# FPGA.net
KiCad netlist of a schematic drawn in Altium Designer
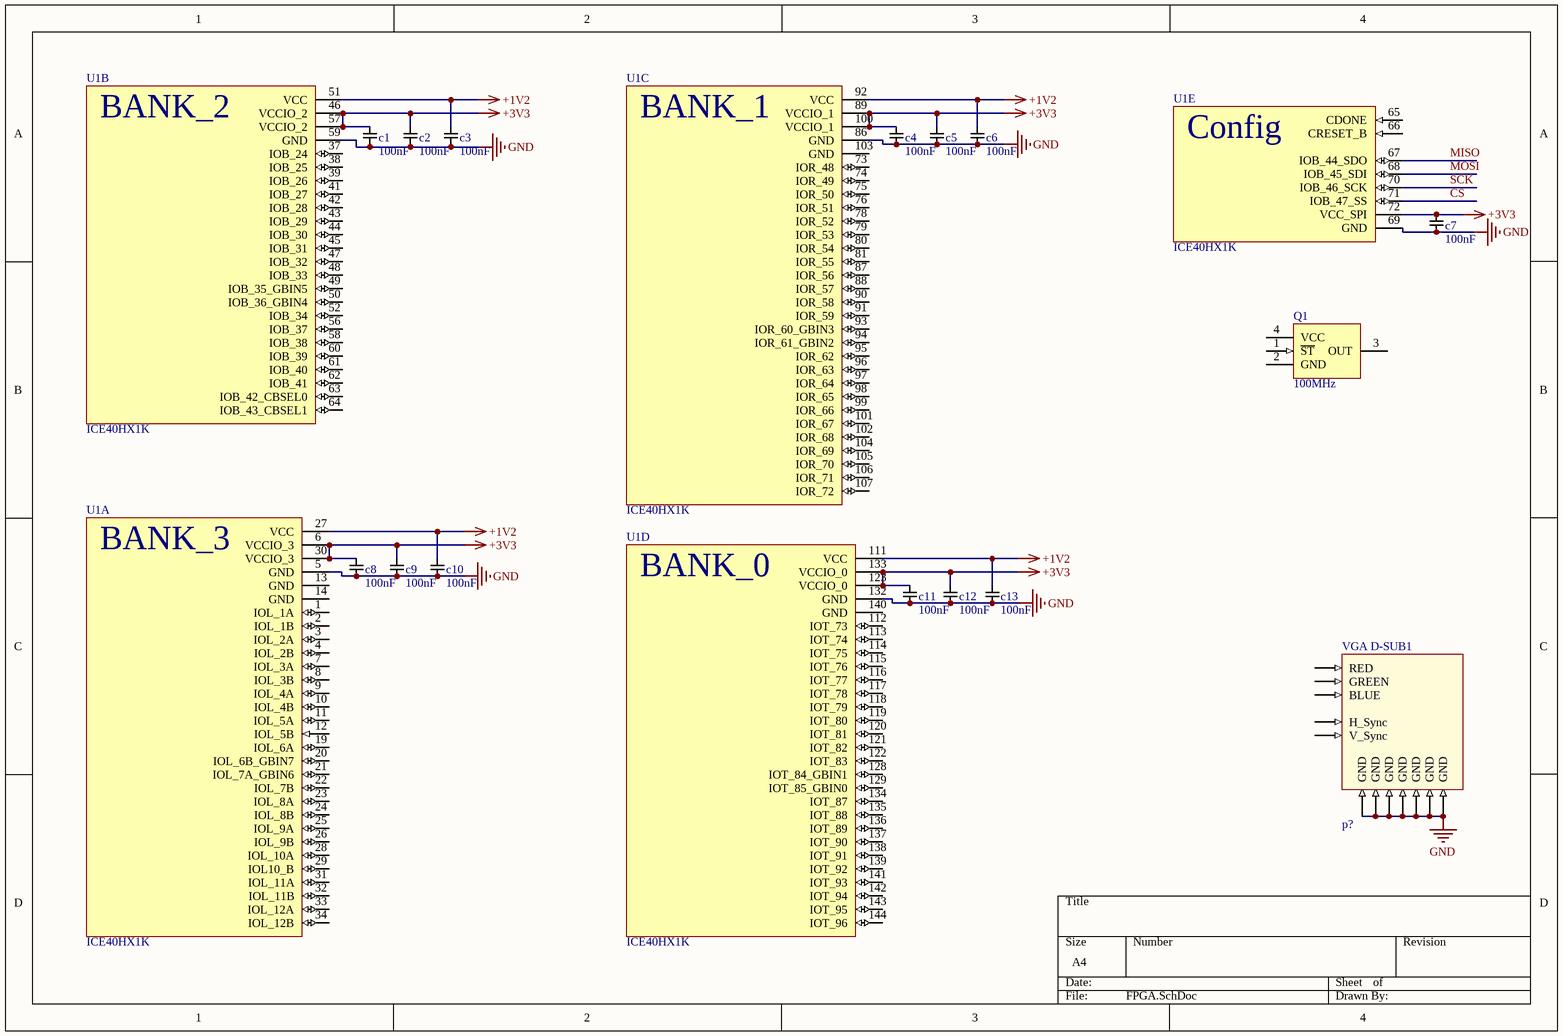
[diagram p0: FPGA.SchDoc]

(export (version "E")
  (design (tool "Eeschema 10.0.6"))
  (components
    (comp (ref "c1")
      (value "100nF")
      (footprint "0603")
      (description "...F")
      (libsource (lib "Generic R-C") (part "0603 Capacitor"))
    )
    (comp (ref "c2")
      (value "100nF")
      (footprint "0603")
      (description "...F")
      (libsource (lib "Generic R-C") (part "0603 Capacitor"))
    )
    (comp (ref "c3")
      (value "100nF")
      (footprint "0603")
      (description "...F")
      (libsource (lib "Generic R-C") (part "0603 Capacitor"))
    )
    (comp (ref "c4")
      (value "100nF")
      (footprint "0603")
      (description "...F")
      (libsource (lib "Generic R-C") (part "0603 Capacitor"))
    )
    (comp (ref "c5")
      (value "100nF")
      (footprint "0603")
      (description "...F")
      (libsource (lib "Generic R-C") (part "0603 Capacitor"))
    )
    (comp (ref "c6")
      (value "100nF")
      (footprint "0603")
      (description "...F")
      (libsource (lib "Generic R-C") (part "0603 Capacitor"))
    )
    (comp (ref "c7")
      (value "100nF")
      (footprint "0603")
      (description "...F")
      (libsource (lib "Generic R-C") (part "0603 Capacitor"))
    )
    (comp (ref "c8")
      (value "100nF")
      (footprint "0603")
      (description "...F")
      (libsource (lib "Generic R-C") (part "0603 Capacitor"))
    )
    (comp (ref "c9")
      (value "100nF")
      (footprint "0603")
      (description "...F")
      (libsource (lib "Generic R-C") (part "0603 Capacitor"))
    )
    (comp (ref "c10")
      (value "100nF")
      (footprint "0603")
      (description "...F")
      (libsource (lib "Generic R-C") (part "0603 Capacitor"))
    )
    (comp (ref "c11")
      (value "100nF")
      (footprint "0603")
      (description "...F")
      (libsource (lib "Generic R-C") (part "0603 Capacitor"))
    )
    (comp (ref "c12")
      (value "100nF")
      (footprint "0603")
      (description "...F")
      (libsource (lib "Generic R-C") (part "0603 Capacitor"))
    )
    (comp (ref "c13")
      (value "100nF")
      (footprint "0603")
      (description "...F")
      (libsource (lib "Generic R-C") (part "0603 Capacitor"))
    )
    (comp (ref "Q1")
      (value "100MHz")
      (footprint "Crystal Oscillator-2.5X2mm")
      (description "Crystal Oscillator")
      (libsource (lib "Seiko Epson Corp.") (part "SG-210S*H"))
    )
    (comp (ref "U1")
      (value "ICE40HX1K")
      (footprint "TQFP-144")
      (description "ICE40 FPGA TQFP-144")
      (libsource (lib "Lattice") (part "ICE40HX1K"))
    )
    (comp (ref "VGA D-SUB1")
      (value "p?")
      (footprint "SUB-D15_VGA")
      (description "VGA receptor")
      (libsource (lib "EDAC") (part "VGA connector"))
    )
  )
  (nets
    (net (code "1") (name "+1V2") (class "Default")
      (node (ref "U1") (pin "111") (pinfunction "VCC_111") (pintype "power_in"))
      (node (ref "U1") (pin "27") (pinfunction "VCC_27") (pintype "power_in"))
      (node (ref "U1") (pin "51") (pinfunction "VCC_51") (pintype "power_in"))
      (node (ref "U1") (pin "92") (pinfunction "VCC_92") (pintype "power_in"))
      (node (ref "c10") (pin "2") (pinfunction "2_2") (pintype "passive"))
      (node (ref "c13") (pin "2") (pinfunction "2_2") (pintype "passive"))
      (node (ref "c3") (pin "2") (pinfunction "2_2") (pintype "passive"))
      (node (ref "c6") (pin "2") (pinfunction "2_2") (pintype "passive"))
    )
    (net (code "2") (name "+3V3") (class "Default")
      (node (ref "U1") (pin "100") (pinfunction "VCCIO_1_100") (pintype "power_in"))
      (node (ref "U1") (pin "123") (pinfunction "VCCIO_0_123") (pintype "power_in"))
      (node (ref "U1") (pin "133") (pinfunction "VCCIO_0_133") (pintype "power_in"))
      (node (ref "U1") (pin "30") (pinfunction "VCCIO_3_30") (pintype "power_in"))
      (node (ref "U1") (pin "46") (pinfunction "VCCIO_2_46") (pintype "power_in"))
      (node (ref "U1") (pin "57") (pinfunction "VCCIO_2_57") (pintype "power_in"))
      (node (ref "U1") (pin "6") (pinfunction "VCCIO_3_6") (pintype "power_in"))
      (node (ref "U1") (pin "72") (pinfunction "VCC_SPI_72") (pintype "power_in"))
      (node (ref "U1") (pin "89") (pinfunction "VCCIO_1_89") (pintype "power_in"))
      (node (ref "c1") (pin "2") (pinfunction "2_2") (pintype "passive"))
      (node (ref "c11") (pin "2") (pinfunction "2_2") (pintype "passive"))
      (node (ref "c12") (pin "2") (pinfunction "2_2") (pintype "passive"))
      (node (ref "c2") (pin "2") (pinfunction "2_2") (pintype "passive"))
      (node (ref "c4") (pin "2") (pinfunction "2_2") (pintype "passive"))
      (node (ref "c5") (pin "2") (pinfunction "2_2") (pintype "passive"))
      (node (ref "c7") (pin "2") (pinfunction "2_2") (pintype "passive"))
      (node (ref "c8") (pin "2") (pinfunction "2_2") (pintype "passive"))
      (node (ref "c9") (pin "2") (pinfunction "2_2") (pintype "passive"))
    )
    (net (code "3") (name "/MISO") (class "Default")
      (node (ref "U1") (pin "67") (pinfunction "IOB_44_SDO_67") (pintype "bidirectional"))
    )
    (net (code "4") (name "/MOSI") (class "Default")
      (node (ref "U1") (pin "68") (pinfunction "IOB_45_SDI_68") (pintype "bidirectional"))
    )
    (net (code "5") (name "/SCK") (class "Default")
      (node (ref "U1") (pin "70") (pinfunction "IOB_46_SCK_70") (pintype "bidirectional"))
    )
    (net (code "6") (name "/~{CS}") (class "Default")
      (node (ref "U1") (pin "71") (pinfunction "IOB_47_SS_71") (pintype "bidirectional"))
    )
    (net (code "7") (name "GND") (class "Default")
      (node (ref "U1") (pin "132") (pinfunction "GND_132") (pintype "power_in"))
      (node (ref "U1") (pin "5") (pinfunction "GND_5") (pintype "power_in"))
      (node (ref "U1") (pin "59") (pinfunction "GND_59") (pintype "power_in"))
      (node (ref "U1") (pin "69") (pinfunction "GND_69") (pintype "power_in"))
      (node (ref "U1") (pin "86") (pinfunction "GND_86") (pintype "power_in"))
      (node (ref "VGA D-SUB1") (pin "10") (pinfunction "GND_10") (pintype "input"))
      (node (ref "VGA D-SUB1") (pin "16") (pinfunction "GND_16") (pintype "input"))
      (node (ref "VGA D-SUB1") (pin "17") (pinfunction "GND_17") (pintype "input"))
      (node (ref "VGA D-SUB1") (pin "5") (pinfunction "GND_5") (pintype "input"))
      (node (ref "VGA D-SUB1") (pin "6") (pinfunction "GND_6") (pintype "input"))
      (node (ref "VGA D-SUB1") (pin "7") (pinfunction "GND_7") (pintype "input"))
      (node (ref "VGA D-SUB1") (pin "8") (pinfunction "GND_8") (pintype "input"))
      (node (ref "c1") (pin "1") (pinfunction "1_1") (pintype "passive"))
      (node (ref "c10") (pin "1") (pinfunction "1_1") (pintype "passive"))
      (node (ref "c11") (pin "1") (pinfunction "1_1") (pintype "passive"))
      (node (ref "c12") (pin "1") (pinfunction "1_1") (pintype "passive"))
      (node (ref "c13") (pin "1") (pinfunction "1_1") (pintype "passive"))
      (node (ref "c2") (pin "1") (pinfunction "1_1") (pintype "passive"))
      (node (ref "c3") (pin "1") (pinfunction "1_1") (pintype "passive"))
      (node (ref "c4") (pin "1") (pinfunction "1_1") (pintype "passive"))
      (node (ref "c5") (pin "1") (pinfunction "1_1") (pintype "passive"))
      (node (ref "c6") (pin "1") (pinfunction "1_1") (pintype "passive"))
      (node (ref "c7") (pin "1") (pinfunction "1_1") (pintype "passive"))
      (node (ref "c8") (pin "1") (pinfunction "1_1") (pintype "passive"))
      (node (ref "c9") (pin "1") (pinfunction "1_1") (pintype "passive"))
    )
    (net (code "8") (name "unconnected-(Q1-GND-Pad2)") (class "Default")
      (node (ref "Q1") (pin "2") (pinfunction "GND_2") (pintype "power_in"))
    )
    (net (code "9") (name "unconnected-(Q1-OUT-Pad3)") (class "Default")
      (node (ref "Q1") (pin "3") (pinfunction "OUT_3") (pintype "power_in"))
    )
    (net (code "10") (name "unconnected-(Q1-VCC-Pad4)") (class "Default")
      (node (ref "Q1") (pin "4") (pinfunction "VCC_4") (pintype "power_in"))
    )
    (net (code "11") (name "unconnected-(Q1-~{ST}-Pad1)") (class "Default")
      (node (ref "Q1") (pin "1") (pinfunction "~{ST}_1") (pintype "input"))
    )
    (net (code "12") (name "unconnected-(U1A-GND-Pad13)") (class "Default")
      (node (ref "U1") (pin "13") (pinfunction "GND_13") (pintype "power_in"))
    )
    (net (code "13") (name "unconnected-(U1A-GND-Pad14)") (class "Default")
      (node (ref "U1") (pin "14") (pinfunction "GND_14") (pintype "power_in"))
    )
    (net (code "14") (name "unconnected-(U1A-IOL10_B-Pad29)") (class "Default")
      (node (ref "U1") (pin "29") (pinfunction "IOL10_B_29") (pintype "bidirectional"))
    )
    (net (code "15") (name "unconnected-(U1A-IOL_1A-Pad1)") (class "Default")
      (node (ref "U1") (pin "1") (pinfunction "IOL_1A_1") (pintype "bidirectional"))
    )
    (net (code "16") (name "unconnected-(U1A-IOL_1B-Pad2)") (class "Default")
      (node (ref "U1") (pin "2") (pinfunction "IOL_1B_2") (pintype "bidirectional"))
    )
    (net (code "17") (name "unconnected-(U1A-IOL_2A-Pad3)") (class "Default")
      (node (ref "U1") (pin "3") (pinfunction "IOL_2A_3") (pintype "bidirectional"))
    )
    (net (code "18") (name "unconnected-(U1A-IOL_2B-Pad4)") (class "Default")
      (node (ref "U1") (pin "4") (pinfunction "IOL_2B_4") (pintype "bidirectional"))
    )
    (net (code "19") (name "unconnected-(U1A-IOL_3A-Pad7)") (class "Default")
      (node (ref "U1") (pin "7") (pinfunction "IOL_3A_7") (pintype "bidirectional"))
    )
    (net (code "20") (name "unconnected-(U1A-IOL_3B-Pad8)") (class "Default")
      (node (ref "U1") (pin "8") (pinfunction "IOL_3B_8") (pintype "bidirectional"))
    )
    (net (code "21") (name "unconnected-(U1A-IOL_4A-Pad9)") (class "Default")
      (node (ref "U1") (pin "9") (pinfunction "IOL_4A_9") (pintype "bidirectional"))
    )
    (net (code "22") (name "unconnected-(U1A-IOL_4B-Pad10)") (class "Default")
      (node (ref "U1") (pin "10") (pinfunction "IOL_4B_10") (pintype "bidirectional"))
    )
    (net (code "23") (name "unconnected-(U1A-IOL_5A-Pad11)") (class "Default")
      (node (ref "U1") (pin "11") (pinfunction "IOL_5A_11") (pintype "bidirectional"))
    )
    (net (code "24") (name "unconnected-(U1A-IOL_5B-Pad12)") (class "Default")
      (node (ref "U1") (pin "12") (pinfunction "IOL_5B_12") (pintype "input"))
    )
    (net (code "25") (name "unconnected-(U1A-IOL_6A-Pad19)") (class "Default")
      (node (ref "U1") (pin "19") (pinfunction "IOL_6A_19") (pintype "bidirectional"))
    )
    (net (code "26") (name "unconnected-(U1A-IOL_6B_GBIN7-Pad20)") (class "Default")
      (node (ref "U1") (pin "20") (pinfunction "IOL_6B_GBIN7_20") (pintype "bidirectional"))
    )
    (net (code "27") (name "unconnected-(U1A-IOL_7A_GBIN6-Pad21)") (class "Default")
      (node (ref "U1") (pin "21") (pinfunction "IOL_7A_GBIN6_21") (pintype "bidirectional"))
    )
    (net (code "28") (name "unconnected-(U1A-IOL_7B-Pad22)") (class "Default")
      (node (ref "U1") (pin "22") (pinfunction "IOL_7B_22") (pintype "bidirectional"))
    )
    (net (code "29") (name "unconnected-(U1A-IOL_8A-Pad23)") (class "Default")
      (node (ref "U1") (pin "23") (pinfunction "IOL_8A_23") (pintype "bidirectional"))
    )
    (net (code "30") (name "unconnected-(U1A-IOL_8B-Pad24)") (class "Default")
      (node (ref "U1") (pin "24") (pinfunction "IOL_8B_24") (pintype "bidirectional"))
    )
    (net (code "31") (name "unconnected-(U1A-IOL_9A-Pad25)") (class "Default")
      (node (ref "U1") (pin "25") (pinfunction "IOL_9A_25") (pintype "bidirectional"))
    )
    (net (code "32") (name "unconnected-(U1A-IOL_9B-Pad26)") (class "Default")
      (node (ref "U1") (pin "26") (pinfunction "IOL_9B_26") (pintype "bidirectional"))
    )
    (net (code "33") (name "unconnected-(U1A-IOL_10A-Pad28)") (class "Default")
      (node (ref "U1") (pin "28") (pinfunction "IOL_10A_28") (pintype "bidirectional"))
    )
    (net (code "34") (name "unconnected-(U1A-IOL_11A-Pad31)") (class "Default")
      (node (ref "U1") (pin "31") (pinfunction "IOL_11A_31") (pintype "bidirectional"))
    )
    (net (code "35") (name "unconnected-(U1A-IOL_11B-Pad32)") (class "Default")
      (node (ref "U1") (pin "32") (pinfunction "IOL_11B_32") (pintype "bidirectional"))
    )
    (net (code "36") (name "unconnected-(U1A-IOL_12A-Pad33)") (class "Default")
      (node (ref "U1") (pin "33") (pinfunction "IOL_12A_33") (pintype "bidirectional"))
    )
    (net (code "37") (name "unconnected-(U1A-IOL_12B-Pad34)") (class "Default")
      (node (ref "U1") (pin "34") (pinfunction "IOL_12B_34") (pintype "bidirectional"))
    )
    (net (code "38") (name "unconnected-(U1B-IOB_24-Pad37)") (class "Default")
      (node (ref "U1") (pin "37") (pinfunction "IOB_24_37") (pintype "bidirectional"))
    )
    (net (code "39") (name "unconnected-(U1B-IOB_25-Pad38)") (class "Default")
      (node (ref "U1") (pin "38") (pinfunction "IOB_25_38") (pintype "bidirectional"))
    )
    (net (code "40") (name "unconnected-(U1B-IOB_26-Pad39)") (class "Default")
      (node (ref "U1") (pin "39") (pinfunction "IOB_26_39") (pintype "bidirectional"))
    )
    (net (code "41") (name "unconnected-(U1B-IOB_27-Pad41)") (class "Default")
      (node (ref "U1") (pin "41") (pinfunction "IOB_27_41") (pintype "bidirectional"))
    )
    (net (code "42") (name "unconnected-(U1B-IOB_28-Pad42)") (class "Default")
      (node (ref "U1") (pin "42") (pinfunction "IOB_28_42") (pintype "bidirectional"))
    )
    (net (code "43") (name "unconnected-(U1B-IOB_29-Pad43)") (class "Default")
      (node (ref "U1") (pin "43") (pinfunction "IOB_29_43") (pintype "bidirectional"))
    )
    (net (code "44") (name "unconnected-(U1B-IOB_30-Pad44)") (class "Default")
      (node (ref "U1") (pin "44") (pinfunction "IOB_30_44") (pintype "bidirectional"))
    )
    (net (code "45") (name "unconnected-(U1B-IOB_31-Pad45)") (class "Default")
      (node (ref "U1") (pin "45") (pinfunction "IOB_31_45") (pintype "bidirectional"))
    )
    (net (code "46") (name "unconnected-(U1B-IOB_32-Pad47)") (class "Default")
      (node (ref "U1") (pin "47") (pinfunction "IOB_32_47") (pintype "bidirectional"))
    )
    (net (code "47") (name "unconnected-(U1B-IOB_33-Pad48)") (class "Default")
      (node (ref "U1") (pin "48") (pinfunction "IOB_33_48") (pintype "bidirectional"))
    )
    (net (code "48") (name "unconnected-(U1B-IOB_34-Pad52)") (class "Default")
      (node (ref "U1") (pin "52") (pinfunction "IOB_34_52") (pintype "bidirectional"))
    )
    (net (code "49") (name "unconnected-(U1B-IOB_35_GBIN5-Pad49)") (class "Default")
      (node (ref "U1") (pin "49") (pinfunction "IOB_35_GBIN5_49") (pintype "bidirectional"))
    )
    (net (code "50") (name "unconnected-(U1B-IOB_36_GBIN4-Pad50)") (class "Default")
      (node (ref "U1") (pin "50") (pinfunction "IOB_36_GBIN4_50") (pintype "bidirectional"))
    )
    (net (code "51") (name "unconnected-(U1B-IOB_37-Pad56)") (class "Default")
      (node (ref "U1") (pin "56") (pinfunction "IOB_37_56") (pintype "bidirectional"))
    )
    (net (code "52") (name "unconnected-(U1B-IOB_38-Pad58)") (class "Default")
      (node (ref "U1") (pin "58") (pinfunction "IOB_38_58") (pintype "bidirectional"))
    )
    (net (code "53") (name "unconnected-(U1B-IOB_39-Pad60)") (class "Default")
      (node (ref "U1") (pin "60") (pinfunction "IOB_39_60") (pintype "bidirectional"))
    )
    (net (code "54") (name "unconnected-(U1B-IOB_40-Pad61)") (class "Default")
      (node (ref "U1") (pin "61") (pinfunction "IOB_40_61") (pintype "bidirectional"))
    )
    (net (code "55") (name "unconnected-(U1B-IOB_41-Pad62)") (class "Default")
      (node (ref "U1") (pin "62") (pinfunction "IOB_41_62") (pintype "bidirectional"))
    )
    (net (code "56") (name "unconnected-(U1B-IOB_42_CBSEL0-Pad63)") (class "Default")
      (node (ref "U1") (pin "63") (pinfunction "IOB_42_CBSEL0_63") (pintype "bidirectional"))
    )
    (net (code "57") (name "unconnected-(U1B-IOB_43_CBSEL1-Pad64)") (class "Default")
      (node (ref "U1") (pin "64") (pinfunction "IOB_43_CBSEL1_64") (pintype "bidirectional"))
    )
    (net (code "58") (name "unconnected-(U1C-GND-Pad103)") (class "Default")
      (node (ref "U1") (pin "103") (pinfunction "GND_103") (pintype "power_in"))
    )
    (net (code "59") (name "unconnected-(U1C-IOR_48-Pad73)") (class "Default")
      (node (ref "U1") (pin "73") (pinfunction "IOR_48_73") (pintype "bidirectional"))
    )
    (net (code "60") (name "unconnected-(U1C-IOR_49-Pad74)") (class "Default")
      (node (ref "U1") (pin "74") (pinfunction "IOR_49_74") (pintype "bidirectional"))
    )
    (net (code "61") (name "unconnected-(U1C-IOR_50-Pad75)") (class "Default")
      (node (ref "U1") (pin "75") (pinfunction "IOR_50_75") (pintype "bidirectional"))
    )
    (net (code "62") (name "unconnected-(U1C-IOR_51-Pad76)") (class "Default")
      (node (ref "U1") (pin "76") (pinfunction "IOR_51_76") (pintype "bidirectional"))
    )
    (net (code "63") (name "unconnected-(U1C-IOR_52-Pad78)") (class "Default")
      (node (ref "U1") (pin "78") (pinfunction "IOR_52_78") (pintype "bidirectional"))
    )
    (net (code "64") (name "unconnected-(U1C-IOR_53-Pad79)") (class "Default")
      (node (ref "U1") (pin "79") (pinfunction "IOR_53_79") (pintype "bidirectional"))
    )
    (net (code "65") (name "unconnected-(U1C-IOR_54-Pad80)") (class "Default")
      (node (ref "U1") (pin "80") (pinfunction "IOR_54_80") (pintype "bidirectional"))
    )
    (net (code "66") (name "unconnected-(U1C-IOR_55-Pad81)") (class "Default")
      (node (ref "U1") (pin "81") (pinfunction "IOR_55_81") (pintype "bidirectional"))
    )
    (net (code "67") (name "unconnected-(U1C-IOR_56-Pad87)") (class "Default")
      (node (ref "U1") (pin "87") (pinfunction "IOR_56_87") (pintype "bidirectional"))
    )
    (net (code "68") (name "unconnected-(U1C-IOR_57-Pad88)") (class "Default")
      (node (ref "U1") (pin "88") (pinfunction "IOR_57_88") (pintype "bidirectional"))
    )
    (net (code "69") (name "unconnected-(U1C-IOR_58-Pad90)") (class "Default")
      (node (ref "U1") (pin "90") (pinfunction "IOR_58_90") (pintype "bidirectional"))
    )
    (net (code "70") (name "unconnected-(U1C-IOR_59-Pad91)") (class "Default")
      (node (ref "U1") (pin "91") (pinfunction "IOR_59_91") (pintype "bidirectional"))
    )
    (net (code "71") (name "unconnected-(U1C-IOR_60_GBIN3-Pad93)") (class "Default")
      (node (ref "U1") (pin "93") (pinfunction "IOR_60_GBIN3_93") (pintype "bidirectional"))
    )
    (net (code "72") (name "unconnected-(U1C-IOR_61_GBIN2-Pad94)") (class "Default")
      (node (ref "U1") (pin "94") (pinfunction "IOR_61_GBIN2_94") (pintype "bidirectional"))
    )
    (net (code "73") (name "unconnected-(U1C-IOR_62-Pad95)") (class "Default")
      (node (ref "U1") (pin "95") (pinfunction "IOR_62_95") (pintype "bidirectional"))
    )
    (net (code "74") (name "unconnected-(U1C-IOR_63-Pad96)") (class "Default")
      (node (ref "U1") (pin "96") (pinfunction "IOR_63_96") (pintype "bidirectional"))
    )
    (net (code "75") (name "unconnected-(U1C-IOR_64-Pad97)") (class "Default")
      (node (ref "U1") (pin "97") (pinfunction "IOR_64_97") (pintype "bidirectional"))
    )
    (net (code "76") (name "unconnected-(U1C-IOR_65-Pad98)") (class "Default")
      (node (ref "U1") (pin "98") (pinfunction "IOR_65_98") (pintype "bidirectional"))
    )
    (net (code "77") (name "unconnected-(U1C-IOR_66-Pad99)") (class "Default")
      (node (ref "U1") (pin "99") (pinfunction "IOR_66_99") (pintype "bidirectional"))
    )
    (net (code "78") (name "unconnected-(U1C-IOR_67-Pad101)") (class "Default")
      (node (ref "U1") (pin "101") (pinfunction "IOR_67_101") (pintype "bidirectional"))
    )
    (net (code "79") (name "unconnected-(U1C-IOR_68-Pad102)") (class "Default")
      (node (ref "U1") (pin "102") (pinfunction "IOR_68_102") (pintype "bidirectional"))
    )
    (net (code "80") (name "unconnected-(U1C-IOR_69-Pad104)") (class "Default")
      (node (ref "U1") (pin "104") (pinfunction "IOR_69_104") (pintype "bidirectional"))
    )
    (net (code "81") (name "unconnected-(U1C-IOR_70-Pad105)") (class "Default")
      (node (ref "U1") (pin "105") (pinfunction "IOR_70_105") (pintype "bidirectional"))
    )
    (net (code "82") (name "unconnected-(U1C-IOR_71-Pad106)") (class "Default")
      (node (ref "U1") (pin "106") (pinfunction "IOR_71_106") (pintype "bidirectional"))
    )
    (net (code "83") (name "unconnected-(U1C-IOR_72-Pad107)") (class "Default")
      (node (ref "U1") (pin "107") (pinfunction "IOR_72_107") (pintype "bidirectional"))
    )
    (net (code "84") (name "unconnected-(U1D-GND-Pad140)") (class "Default")
      (node (ref "U1") (pin "140") (pinfunction "GND_140") (pintype "power_in"))
    )
    (net (code "85") (name "unconnected-(U1D-IOT_73-Pad112)") (class "Default")
      (node (ref "U1") (pin "112") (pinfunction "IOT_73_112") (pintype "bidirectional"))
    )
    (net (code "86") (name "unconnected-(U1D-IOT_74-Pad113)") (class "Default")
      (node (ref "U1") (pin "113") (pinfunction "IOT_74_113") (pintype "bidirectional"))
    )
    (net (code "87") (name "unconnected-(U1D-IOT_75-Pad114)") (class "Default")
      (node (ref "U1") (pin "114") (pinfunction "IOT_75_114") (pintype "bidirectional"))
    )
    (net (code "88") (name "unconnected-(U1D-IOT_76-Pad115)") (class "Default")
      (node (ref "U1") (pin "115") (pinfunction "IOT_76_115") (pintype "bidirectional"))
    )
    (net (code "89") (name "unconnected-(U1D-IOT_77-Pad116)") (class "Default")
      (node (ref "U1") (pin "116") (pinfunction "IOT_77_116") (pintype "bidirectional"))
    )
    (net (code "90") (name "unconnected-(U1D-IOT_78-Pad117)") (class "Default")
      (node (ref "U1") (pin "117") (pinfunction "IOT_78_117") (pintype "bidirectional"))
    )
    (net (code "91") (name "unconnected-(U1D-IOT_79-Pad118)") (class "Default")
      (node (ref "U1") (pin "118") (pinfunction "IOT_79_118") (pintype "bidirectional"))
    )
    (net (code "92") (name "unconnected-(U1D-IOT_80-Pad119)") (class "Default")
      (node (ref "U1") (pin "119") (pinfunction "IOT_80_119") (pintype "bidirectional"))
    )
    (net (code "93") (name "unconnected-(U1D-IOT_81-Pad120)") (class "Default")
      (node (ref "U1") (pin "120") (pinfunction "IOT_81_120") (pintype "bidirectional"))
    )
    (net (code "94") (name "unconnected-(U1D-IOT_82-Pad121)") (class "Default")
      (node (ref "U1") (pin "121") (pinfunction "IOT_82_121") (pintype "bidirectional"))
    )
    (net (code "95") (name "unconnected-(U1D-IOT_83-Pad122)") (class "Default")
      (node (ref "U1") (pin "122") (pinfunction "IOT_83_122") (pintype "bidirectional"))
    )
    (net (code "96") (name "unconnected-(U1D-IOT_84_GBIN1-Pad128)") (class "Default")
      (node (ref "U1") (pin "128") (pinfunction "IOT_84_GBIN1_128") (pintype "bidirectional"))
    )
    (net (code "97") (name "unconnected-(U1D-IOT_85_GBIN0-Pad129)") (class "Default")
      (node (ref "U1") (pin "129") (pinfunction "IOT_85_GBIN0_129") (pintype "bidirectional"))
    )
    (net (code "98") (name "unconnected-(U1D-IOT_87-Pad134)") (class "Default")
      (node (ref "U1") (pin "134") (pinfunction "IOT_87_134") (pintype "bidirectional"))
    )
    (net (code "99") (name "unconnected-(U1D-IOT_88-Pad135)") (class "Default")
      (node (ref "U1") (pin "135") (pinfunction "IOT_88_135") (pintype "bidirectional"))
    )
    (net (code "100") (name "unconnected-(U1D-IOT_89-Pad136)") (class "Default")
      (node (ref "U1") (pin "136") (pinfunction "IOT_89_136") (pintype "bidirectional"))
    )
    (net (code "101") (name "unconnected-(U1D-IOT_90-Pad137)") (class "Default")
      (node (ref "U1") (pin "137") (pinfunction "IOT_90_137") (pintype "bidirectional"))
    )
    (net (code "102") (name "unconnected-(U1D-IOT_91-Pad138)") (class "Default")
      (node (ref "U1") (pin "138") (pinfunction "IOT_91_138") (pintype "bidirectional"))
    )
    (net (code "103") (name "unconnected-(U1D-IOT_92-Pad139)") (class "Default")
      (node (ref "U1") (pin "139") (pinfunction "IOT_92_139") (pintype "bidirectional"))
    )
    (net (code "104") (name "unconnected-(U1D-IOT_93-Pad141)") (class "Default")
      (node (ref "U1") (pin "141") (pinfunction "IOT_93_141") (pintype "bidirectional"))
    )
    (net (code "105") (name "unconnected-(U1D-IOT_94-Pad142)") (class "Default")
      (node (ref "U1") (pin "142") (pinfunction "IOT_94_142") (pintype "bidirectional"))
    )
    (net (code "106") (name "unconnected-(U1D-IOT_95-Pad143)") (class "Default")
      (node (ref "U1") (pin "143") (pinfunction "IOT_95_143") (pintype "bidirectional"))
    )
    (net (code "107") (name "unconnected-(U1D-IOT_96-Pad144)") (class "Default")
      (node (ref "U1") (pin "144") (pinfunction "IOT_96_144") (pintype "bidirectional"))
    )
    (net (code "108") (name "unconnected-(U1E-CDONE-Pad65)") (class "Default")
      (node (ref "U1") (pin "65") (pinfunction "CDONE_65") (pintype "input"))
    )
    (net (code "109") (name "unconnected-(U1E-CRESET_B-Pad66)") (class "Default")
      (node (ref "U1") (pin "66") (pinfunction "CRESET_B_66") (pintype "input"))
    )
    (net (code "110") (name "unconnected-(VGA D-SUB1-BLUE-Pad3)") (class "Default")
      (node (ref "VGA D-SUB1") (pin "3") (pinfunction "BLUE_3") (pintype "input"))
    )
    (net (code "111") (name "unconnected-(VGA D-SUB1-GREEN-Pad2)") (class "Default")
      (node (ref "VGA D-SUB1") (pin "2") (pinfunction "GREEN_2") (pintype "input"))
    )
    (net (code "112") (name "unconnected-(VGA D-SUB1-H_Sync-Pad13)") (class "Default")
      (node (ref "VGA D-SUB1") (pin "13") (pinfunction "H_Sync_13") (pintype "input"))
    )
    (net (code "113") (name "unconnected-(VGA D-SUB1-RED-Pad1)") (class "Default")
      (node (ref "VGA D-SUB1") (pin "1") (pinfunction "RED_1") (pintype "input"))
    )
    (net (code "114") (name "unconnected-(VGA D-SUB1-V_Sync-Pad14)") (class "Default")
      (node (ref "VGA D-SUB1") (pin "14") (pinfunction "V_Sync_14") (pintype "input"))
    )
  )
)
